# gesture_control_robot_tx.net
KiCad netlist of a schematic drawn in EAGLE
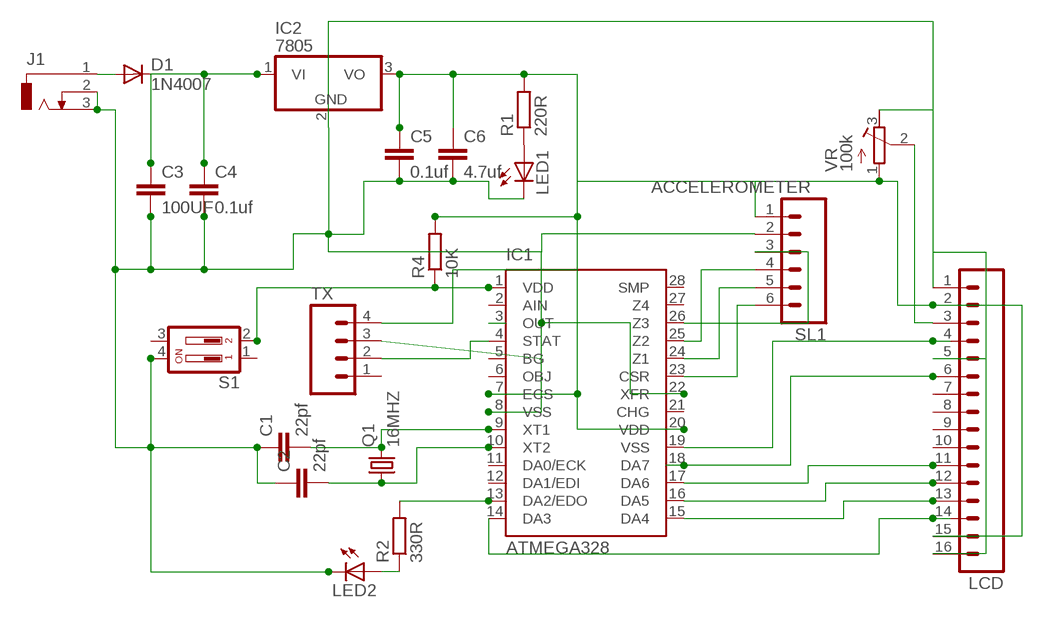
[diagram p0: schematic, sheet 1]

(export (version "E")
  (design (tool "Eeschema 10.0.6"))
  (components
    (comp (ref "C1")
      (value "22pf")
      (footprint "eagle-import:C2.5-2")
      (libsource (lib "eagle-import") (part "C2.5/2"))
    )
    (comp (ref "C2")
      (value "22pf")
      (footprint "eagle-import:C2.5-2")
      (libsource (lib "eagle-import") (part "C2.5/2"))
    )
    (comp (ref "C3")
      (value "100UF")
      (footprint "eagle-import:C2.5-2")
      (libsource (lib "eagle-import") (part "C2.5/2"))
    )
    (comp (ref "C4")
      (value "0.1uf")
      (footprint "eagle-import:C2.5-2")
      (libsource (lib "eagle-import") (part "C2.5/2"))
    )
    (comp (ref "C5")
      (value "0.1uf")
      (footprint "eagle-import:C2.5-2")
      (libsource (lib "eagle-import") (part "C2.5/2"))
    )
    (comp (ref "C6")
      (value "4.7uf")
      (footprint "eagle-import:C2.5-2")
      (libsource (lib "eagle-import") (part "C2.5/2"))
    )
    (comp (ref "D1")
      (value "1N4007")
      (footprint "eagle-import:DO41-10")
      (libsource (lib "eagle-import") (part "1N4004"))
    )
    (comp (ref "IC1")
      (value "ATMEGA328")
      (footprint "eagle-import:DIL28-3")
      (libsource (lib "eagle-import") (part "QT9701BD"))
    )
    (comp (ref "IC2")
      (value "7805")
      (footprint "eagle-import:TO220V")
      (libsource (lib "eagle-import") (part "78TV6"))
    )
    (comp (ref "J1")
      (value "DCJ0303")
      (footprint "eagle-import:DCJ0303")
      (libsource (lib "eagle-import") (part "DCJ0303"))
    )
    (comp (ref "LCD")
      (value "M16")
      (footprint "eagle-import:16P")
      (libsource (lib "eagle-import") (part "M16"))
    )
    (comp (ref "LED1")
      (value "LED3MM")
      (footprint "eagle-import:LED3MM")
      (libsource (lib "eagle-import") (part "LED3MM"))
    )
    (comp (ref "LED2")
      (value "LED3MM")
      (footprint "eagle-import:LED3MM")
      (libsource (lib "eagle-import") (part "LED3MM"))
    )
    (comp (ref "Q1")
      (value "16MHZ")
      (footprint "eagle-import:HC49_S")
      (libsource (lib "eagle-import") (part "CRYSTALHC49S"))
    )
    (comp (ref "R1")
      (value "220R")
      (footprint "eagle-import:0207_10")
      (libsource (lib "eagle-import") (part "R-EU_0207/10"))
    )
    (comp (ref "R2")
      (value "330R")
      (footprint "eagle-import:0207_10")
      (libsource (lib "eagle-import") (part "R-EU_0207/10"))
    )
    (comp (ref "R4")
      (value "10K")
      (footprint "eagle-import:0207_10")
      (libsource (lib "eagle-import") (part "R-EU_0207/10"))
    )
    (comp (ref "S1")
      (value "DP02")
      (footprint "eagle-import:DP-02")
      (fields (field (name "MPN") "MCDP02"))
      (libsource (lib "eagle-import") (part "DP02"))
    )
    (comp (ref "SL1")
      (value "ACCELEROMETER")
      (footprint "eagle-import:06P")
      (libsource (lib "eagle-import") (part "M06"))
    )
    (comp (ref "TX")
      (value "M04")
      (footprint "eagle-import:04P")
      (libsource (lib "eagle-import") (part "M04"))
    )
    (comp (ref "VR")
      (value "100k")
      (footprint "eagle-import:RTRIM64P")
      (libsource (lib "eagle-import") (part "R-TRIMM64P"))
    )
  )
  (nets
    (net (code "1") (name "Net-(D1-PadA)") (class "Default")
      (node (ref "D1") (pin "A") (pinfunction "A_A") (pintype "passive"))
      (node (ref "J1") (pin "1") (pinfunction "1_1") (pintype "passive"))
    )
    (net (code "2") (name "Net-(IC1-CSR)") (class "Default")
      (node (ref "IC1") (pin "23") (pinfunction "CSR_23") (pintype "output"))
      (node (ref "SL1") (pin "6") (pinfunction "6_6") (pintype "passive"))
    )
    (net (code "3") (name "Net-(IC1-DA2{slash}EDO)") (class "Default")
      (node (ref "IC1") (pin "13") (pinfunction "DA2/EDO_13") (pintype "output"))
      (node (ref "R2") (pin "2") (pinfunction "2_2") (pintype "passive"))
    )
    (net (code "4") (name "Net-(IC1-DA3)") (class "Default")
      (node (ref "IC1") (pin "14") (pinfunction "DA3_14") (pintype "output"))
      (node (ref "LCD") (pin "14") (pinfunction "14_14") (pintype "passive"))
    )
    (net (code "5") (name "Net-(IC1-DA4)") (class "Default")
      (node (ref "IC1") (pin "15") (pinfunction "DA4_15") (pintype "output"))
      (node (ref "LCD") (pin "13") (pinfunction "13_13") (pintype "passive"))
    )
    (net (code "6") (name "Net-(IC1-DA5)") (class "Default")
      (node (ref "IC1") (pin "16") (pinfunction "DA5_16") (pintype "output"))
      (node (ref "LCD") (pin "12") (pinfunction "12_12") (pintype "passive"))
    )
    (net (code "7") (name "Net-(IC1-DA6)") (class "Default")
      (node (ref "IC1") (pin "17") (pinfunction "DA6_17") (pintype "output"))
      (node (ref "LCD") (pin "11") (pinfunction "11_11") (pintype "passive"))
    )
    (net (code "8") (name "Net-(IC1-DA7)") (class "Default")
      (node (ref "IC1") (pin "18") (pinfunction "DA7_18") (pintype "output"))
      (node (ref "LCD") (pin "6") (pinfunction "6_6") (pintype "passive"))
    )
    (net (code "9") (name "Net-(IC1-ECS)") (class "Default")
      (node (ref "C5") (pin "1") (pinfunction "1_1") (pintype "passive"))
      (node (ref "C6") (pin "1") (pinfunction "1_1") (pintype "passive"))
      (node (ref "IC1") (pin "20") (pinfunction "VDD_20") (pintype "input"))
      (node (ref "IC1") (pin "7") (pinfunction "ECS_7") (pintype "output"))
      (node (ref "IC2") (pin "3") (pinfunction "VO_3") (pintype "passive"))
      (node (ref "LCD") (pin "15") (pinfunction "15_15") (pintype "passive"))
      (node (ref "LCD") (pin "2") (pinfunction "2_2") (pintype "passive"))
      (node (ref "R1") (pin "2") (pinfunction "2_2") (pintype "passive"))
      (node (ref "R4") (pin "2") (pinfunction "2_2") (pintype "passive"))
      (node (ref "SL1") (pin "1") (pinfunction "1_1") (pintype "passive"))
      (node (ref "TX") (pin "4") (pinfunction "4_4") (pintype "passive"))
      (node (ref "VR") (pin "1") (pinfunction "E_1") (pintype "passive"))
    )
    (net (code "10") (name "Net-(IC1-STAT)") (class "Default")
      (node (ref "IC1") (pin "4") (pinfunction "STAT_4") (pintype "output"))
      (node (ref "TX") (pin "2") (pinfunction "2_2") (pintype "passive"))
    )
    (net (code "11") (name "Net-(IC1-VDD-Pad1)") (class "Default")
      (node (ref "IC1") (pin "1") (pinfunction "VDD_1") (pintype "input"))
      (node (ref "R4") (pin "1") (pinfunction "1_1") (pintype "passive"))
      (node (ref "S1") (pin "2") (pinfunction "2_2") (pintype "passive"))
    )
    (net (code "12") (name "Net-(IC1-VSS-Pad19)") (class "Default")
      (node (ref "IC1") (pin "19") (pinfunction "VSS_19") (pintype "input"))
      (node (ref "LCD") (pin "4") (pinfunction "4_4") (pintype "passive"))
    )
    (net (code "13") (name "Net-(IC1-XFR)") (class "Default")
      (node (ref "C1") (pin "1") (pinfunction "1_1") (pintype "passive"))
      (node (ref "C2") (pin "1") (pinfunction "1_1") (pintype "passive"))
      (node (ref "C3") (pin "2") (pinfunction "2_2") (pintype "passive"))
      (node (ref "C4") (pin "2") (pinfunction "2_2") (pintype "passive"))
      (node (ref "C5") (pin "2") (pinfunction "2_2") (pintype "passive"))
      (node (ref "C6") (pin "2") (pinfunction "2_2") (pintype "passive"))
      (node (ref "IC1") (pin "22") (pinfunction "XFR_22") (pintype "output"))
      (node (ref "IC1") (pin "8") (pinfunction "VSS_8") (pintype "input"))
      (node (ref "IC2") (pin "2") (pinfunction "GND_2") (pintype "passive"))
      (node (ref "J1") (pin "2") (pinfunction "2_2") (pintype "passive"))
      (node (ref "J1") (pin "3") (pinfunction "3_3") (pintype "passive"))
      (node (ref "LCD") (pin "1") (pinfunction "1_1") (pintype "passive"))
      (node (ref "LCD") (pin "16") (pinfunction "16_16") (pintype "passive"))
      (node (ref "LCD") (pin "5") (pinfunction "5_5") (pintype "passive"))
      (node (ref "LED1") (pin "K") (pinfunction "C_K") (pintype "passive"))
      (node (ref "LED2") (pin "K") (pinfunction "C_K") (pintype "passive"))
      (node (ref "S1") (pin "4") (pinfunction "4_4") (pintype "passive"))
      (node (ref "SL1") (pin "2") (pinfunction "2_2") (pintype "passive"))
      (node (ref "TX") (pin "3") (pinfunction "3_3") (pintype "passive"))
      (node (ref "VR") (pin "3") (pinfunction "A_3") (pintype "passive"))
    )
    (net (code "14") (name "Net-(IC1-XT1)") (class "Default")
      (node (ref "C1") (pin "2") (pinfunction "2_2") (pintype "passive"))
      (node (ref "IC1") (pin "9") (pinfunction "XT1_9") (pintype "input"))
      (node (ref "Q1") (pin "2") (pinfunction "2_2") (pintype "passive"))
    )
    (net (code "15") (name "Net-(IC1-XT2)") (class "Default")
      (node (ref "C2") (pin "2") (pinfunction "2_2") (pintype "passive"))
      (node (ref "IC1") (pin "10") (pinfunction "XT2_10") (pintype "output"))
      (node (ref "Q1") (pin "1") (pinfunction "1_1") (pintype "passive"))
    )
    (net (code "16") (name "Net-(IC1-Z1)") (class "Default")
      (node (ref "IC1") (pin "24") (pinfunction "Z1_24") (pintype "output"))
      (node (ref "SL1") (pin "5") (pinfunction "5_5") (pintype "passive"))
    )
    (net (code "17") (name "Net-(IC1-Z2)") (class "Default")
      (node (ref "IC1") (pin "25") (pinfunction "Z2_25") (pintype "output"))
      (node (ref "SL1") (pin "4") (pinfunction "4_4") (pintype "passive"))
    )
    (net (code "18") (name "Net-(IC1-Z3)") (class "Default")
      (node (ref "IC1") (pin "26") (pinfunction "Z3_26") (pintype "output"))
      (node (ref "SL1") (pin "3") (pinfunction "3_3") (pintype "passive"))
    )
    (net (code "19") (name "Net-(IC2-VI)") (class "Default")
      (node (ref "C3") (pin "1") (pinfunction "1_1") (pintype "passive"))
      (node (ref "C4") (pin "1") (pinfunction "1_1") (pintype "passive"))
      (node (ref "D1") (pin "C") (pinfunction "C_C") (pintype "passive"))
      (node (ref "IC2") (pin "1") (pinfunction "VI_1") (pintype "input"))
    )
    (net (code "20") (name "Net-(LED1-PadA)") (class "Default")
      (node (ref "LED1") (pin "A") (pinfunction "A_A") (pintype "passive"))
      (node (ref "R1") (pin "1") (pinfunction "1_1") (pintype "passive"))
    )
    (net (code "21") (name "Net-(LED2-PadA)") (class "Default")
      (node (ref "LED2") (pin "A") (pinfunction "A_A") (pintype "passive"))
      (node (ref "R2") (pin "1") (pinfunction "1_1") (pintype "passive"))
    )
    (net (code "22") (name "Net-(VR-S)") (class "Default")
      (node (ref "LCD") (pin "3") (pinfunction "3_3") (pintype "passive"))
      (node (ref "VR") (pin "2") (pinfunction "S_2") (pintype "passive"))
    )
    (net (code "23") (name "unconnected-(IC1-AIN-Pad2)") (class "Default")
      (node (ref "IC1") (pin "2") (pinfunction "AIN_2") (pintype "input"))
    )
    (net (code "24") (name "unconnected-(IC1-BG-Pad5)") (class "Default")
      (node (ref "IC1") (pin "5") (pinfunction "BG_5") (pintype "input"))
    )
    (net (code "25") (name "unconnected-(IC1-CHG-Pad21)") (class "Default")
      (node (ref "IC1") (pin "21") (pinfunction "CHG_21") (pintype "output"))
    )
    (net (code "26") (name "unconnected-(IC1-DA0{slash}ECK-Pad11)") (class "Default")
      (node (ref "IC1") (pin "11") (pinfunction "DA0/ECK_11") (pintype "output"))
    )
    (net (code "27") (name "unconnected-(IC1-DA1{slash}EDI-Pad12)") (class "Default")
      (node (ref "IC1") (pin "12") (pinfunction "DA1/EDI_12") (pintype "output"))
    )
    (net (code "28") (name "unconnected-(IC1-OBJ-Pad6)") (class "Default")
      (node (ref "IC1") (pin "6") (pinfunction "OBJ_6") (pintype "input"))
    )
    (net (code "29") (name "unconnected-(IC1-OUT-Pad3)") (class "Default")
      (node (ref "IC1") (pin "3") (pinfunction "OUT_3") (pintype "output"))
    )
    (net (code "30") (name "unconnected-(IC1-SMP-Pad28)") (class "Default")
      (node (ref "IC1") (pin "28") (pinfunction "SMP_28") (pintype "output"))
    )
    (net (code "31") (name "unconnected-(IC1-Z4-Pad27)") (class "Default")
      (node (ref "IC1") (pin "27") (pinfunction "Z4_27") (pintype "output"))
    )
    (net (code "32") (name "unconnected-(LCD-Pad7)") (class "Default")
      (node (ref "LCD") (pin "7") (pinfunction "7_7") (pintype "passive"))
    )
    (net (code "33") (name "unconnected-(LCD-Pad8)") (class "Default")
      (node (ref "LCD") (pin "8") (pinfunction "8_8") (pintype "passive"))
    )
    (net (code "34") (name "unconnected-(LCD-Pad9)") (class "Default")
      (node (ref "LCD") (pin "9") (pinfunction "9_9") (pintype "passive"))
    )
    (net (code "35") (name "unconnected-(LCD-Pad10)") (class "Default")
      (node (ref "LCD") (pin "10") (pinfunction "10_10") (pintype "passive"))
    )
    (net (code "36") (name "unconnected-(S1-Pad1)") (class "Default")
      (node (ref "S1") (pin "1") (pinfunction "1_1") (pintype "passive"))
    )
    (net (code "37") (name "unconnected-(S1-Pad3)") (class "Default")
      (node (ref "S1") (pin "3") (pinfunction "3_3") (pintype "passive"))
    )
    (net (code "38") (name "unconnected-(TX-Pad1)") (class "Default")
      (node (ref "TX") (pin "1") (pinfunction "1_1") (pintype "passive"))
    )
  )
)
